# CH1-Isolation.net
KiCad netlist of a schematic drawn in Altium Designer
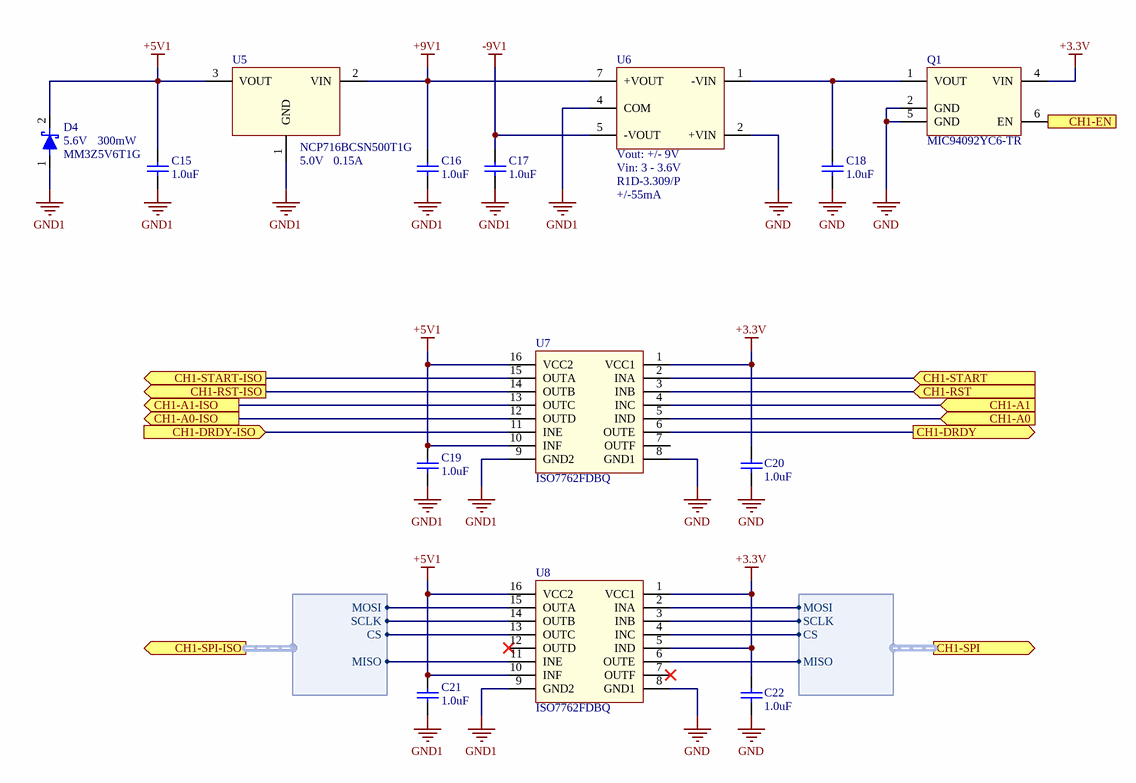
[diagram p0: CH1-Isolation.SchDoc]

(export (version "E")
  (design (tool "Eeschema 10.0.6"))
  (components
    (comp (ref "C15")
      (value "1.0uF")
      (footprint "CAP-0603")
      (description "CAP CER 1uF 25V X7R 0603")
      (fields (field (name "PARTNUMBER") "C0603C105M3RAC7867") (field (name "MANUFACTURER") "Kemet"))
      (libsource (lib "Kemet") (part "C0603C105M3RAC7867"))
    )
    (comp (ref "C16")
      (value "1.0uF")
      (footprint "CAP-0603")
      (description "CAP CER 1uF 25V X7R 0603")
      (fields (field (name "PARTNUMBER") "C0603C105M3RAC7867") (field (name "MANUFACTURER") "Kemet"))
      (libsource (lib "Kemet") (part "C0603C105M3RAC7867"))
    )
    (comp (ref "C17")
      (value "1.0uF")
      (footprint "CAP-0603")
      (description "CAP CER 1uF 25V X7R 0603")
      (fields (field (name "PARTNUMBER") "C0603C105M3RAC7867") (field (name "MANUFACTURER") "Kemet"))
      (libsource (lib "Kemet") (part "C0603C105M3RAC7867"))
    )
    (comp (ref "C18")
      (value "1.0uF")
      (footprint "CAP-0603")
      (description "CAP CER 1uF 25V X7R 0603")
      (fields (field (name "PARTNUMBER") "C0603C105M3RAC7867") (field (name "MANUFACTURER") "Kemet"))
      (libsource (lib "Kemet") (part "C0603C105M3RAC7867"))
    )
    (comp (ref "C19")
      (value "1.0uF")
      (footprint "CAP-0603")
      (description "CAP CER 1uF 25V X7R 0603")
      (fields (field (name "PARTNUMBER") "C0603C105M3RAC7867") (field (name "MANUFACTURER") "Kemet"))
      (libsource (lib "Kemet") (part "C0603C105M3RAC7867"))
    )
    (comp (ref "C20")
      (value "1.0uF")
      (footprint "CAP-0603")
      (description "CAP CER 1uF 25V X7R 0603")
      (fields (field (name "PARTNUMBER") "C0603C105M3RAC7867") (field (name "MANUFACTURER") "Kemet"))
      (libsource (lib "Kemet") (part "C0603C105M3RAC7867"))
    )
    (comp (ref "C21")
      (value "1.0uF")
      (footprint "CAP-0603")
      (description "CAP CER 1uF 25V X7R 0603")
      (fields (field (name "PARTNUMBER") "C0603C105M3RAC7867") (field (name "MANUFACTURER") "Kemet"))
      (libsource (lib "Kemet") (part "C0603C105M3RAC7867"))
    )
    (comp (ref "C22")
      (value "1.0uF")
      (footprint "CAP-0603")
      (description "CAP CER 1uF 25V X7R 0603")
      (fields (field (name "PARTNUMBER") "C0603C105M3RAC7867") (field (name "MANUFACTURER") "Kemet"))
      (libsource (lib "Kemet") (part "C0603C105M3RAC7867"))
    )
    (comp (ref "D4")
      (value "MM3Z5V6T1G")
      (footprint "SOD323 - DIODE UNIDIR")
      (description "Schottky Diode 30V 200mA SOT323")
      (fields
        (field (name "MANUFACTURER") "OnSemiconductor")
        (field (name "POWER") "300mW")
        (field (name "VZ") "5.6V")
        (field (name "PARTNUMBER") "MM3Z5V6T1G")
      )
      (libsource (lib "OnSemiconductors") (part "MM3Z5V6T1G"))
    )
    (comp (ref "Q1")
      (value "MIC94092YC6-TR")
      (footprint "TSSOP6")
      (fields (field (name "MANUFACTURER") "Microchip") (field (name "PARTNUMBER") "MIC94092YC6-TR"))
      (libsource (lib "Microchip") (part "MIC94092YC6-TR"))
    )
    (comp (ref "U5")
      (value "NCP716BCSN500T1G")
      (footprint "SOT23-5")
      (description "IC REG LDO 0.5V 0.15A TSOT23-5")
      (fields
        (field (name "MANUFACTURER") "ON Semiconductor")
        (field (name "PARTNUMBER") "NCP716BCSN500T1G")
        (field (name "VOLTAGE") "5.0V")
        (field (name "CURRENT") "0.15A")
      )
      (libsource (lib "OnSemiconductors") (part "NCP716BCSN500T1G"))
    )
    (comp (ref "U6")
      (value "R1D-3.309/P")
      (footprint "RECOM-R1D")
      (description "DC DC CONVERTER +/-9V 1W")
      (fields
        (field (name "MANUFACTURER") "Recom")
        (field (name "VOUT") "+/- 9V")
        (field (name "VIN") "3 - 3.6V")
        (field (name "PART NUMBER") "R1D-3.309/P")
        (field (name "CURRENT") "+/-55mA")
      )
      (libsource (lib "Recom") (part "R1D-3.309/P"))
    )
    (comp (ref "U7")
      (value "ISO7762FDBQ")
      (footprint "SSOP16")
      (description "Digital Isolator, six-channel, 4/2, 16-SSOP")
      (fields (field (name "MANUFACTURER") "Texas Instruments") (field (name "PARTNUMBER") "ISO7762FDBQ"))
      (libsource (lib "TexasInstruments") (part "ISO7762FDBQ"))
    )
    (comp (ref "U8")
      (value "ISO7762FDBQ")
      (footprint "SSOP16")
      (description "Digital Isolator, six-channel, 4/2, 16-SSOP")
      (fields (field (name "MANUFACTURER") "Texas Instruments") (field (name "PARTNUMBER") "ISO7762FDBQ"))
      (libsource (lib "TexasInstruments") (part "ISO7762FDBQ"))
    )
  )
  (nets
    (net (code "3") (name "+3.3V") (class "Default")
      (node (ref "C20") (pin "2") (pinfunction "2_2") (pintype "passive"))
      (node (ref "C22") (pin "2") (pinfunction "2_2") (pintype "passive"))
      (node (ref "Q1") (pin "4") (pinfunction "VIN_4") (pintype "passive"))
      (node (ref "U7") (pin "1") (pinfunction "VCC1_1") (pintype "passive"))
      (node (ref "U8") (pin "1") (pinfunction "VCC1_1") (pintype "passive"))
      (node (ref "U8") (pin "5") (pinfunction "IND_5") (pintype "passive"))
    )
    (net (code "4") (name "+5V1") (class "Default")
      (node (ref "C15") (pin "2") (pinfunction "2_2") (pintype "passive"))
      (node (ref "C19") (pin "2") (pinfunction "2_2") (pintype "passive"))
      (node (ref "C21") (pin "2") (pinfunction "2_2") (pintype "passive"))
      (node (ref "D4") (pin "2") (pinfunction "K_2") (pintype "passive"))
      (node (ref "U5") (pin "3") (pinfunction "VOUT_3") (pintype "passive"))
      (node (ref "U7") (pin "10") (pinfunction "INF_10") (pintype "passive"))
      (node (ref "U7") (pin "16") (pinfunction "VCC2_16") (pintype "passive"))
      (node (ref "U8") (pin "10") (pinfunction "INF_10") (pintype "passive"))
      (node (ref "U8") (pin "16") (pinfunction "VCC2_16") (pintype "passive"))
    )
    (net (code "5") (name "+9V1") (class "Default")
      (node (ref "C16") (pin "2") (pinfunction "2_2") (pintype "passive"))
      (node (ref "U5") (pin "2") (pinfunction "VIN_2") (pintype "passive"))
      (node (ref "U6") (pin "7") (pinfunction "+VOUT_7") (pintype "passive"))
    )
    (net (code "6") (name "-9V1") (class "Default")
      (node (ref "C17") (pin "2") (pinfunction "2_2") (pintype "passive"))
      (node (ref "U6") (pin "5") (pinfunction "-VOUT_5") (pintype "passive"))
    )
    (net (code "7") (name "/CH1-A0") (class "Default")
      (node (ref "U7") (pin "5") (pinfunction "IND_5") (pintype "passive"))
    )
    (net (code "8") (name "/CH1-A0-ISO") (class "Default")
      (node (ref "U7") (pin "12") (pinfunction "OUTD_12") (pintype "passive"))
    )
    (net (code "9") (name "/CH1-A1") (class "Default")
      (node (ref "U7") (pin "4") (pinfunction "INC_4") (pintype "passive"))
    )
    (net (code "10") (name "/CH1-A1-ISO") (class "Default")
      (node (ref "U7") (pin "13") (pinfunction "OUTC_13") (pintype "passive"))
    )
    (net (code "11") (name "/CH1-DRDY") (class "Default")
      (node (ref "U7") (pin "6") (pinfunction "OUTE_6") (pintype "passive"))
    )
    (net (code "12") (name "/CH1-DRDY-ISO") (class "Default")
      (node (ref "U7") (pin "11") (pinfunction "INE_11") (pintype "passive"))
    )
    (net (code "13") (name "/CH1-EN") (class "Default")
      (node (ref "Q1") (pin "6") (pinfunction "EN_6") (pintype "passive"))
    )
    (net (code "14") (name "/CH1-RST") (class "Default")
      (node (ref "U7") (pin "3") (pinfunction "INB_3") (pintype "passive"))
    )
    (net (code "15") (name "/CH1-RST-ISO") (class "Default")
      (node (ref "U7") (pin "14") (pinfunction "OUTB_14") (pintype "passive"))
    )
    (net (code "16") (name "/CH1-START") (class "Default")
      (node (ref "U7") (pin "2") (pinfunction "INA_2") (pintype "passive"))
    )
    (net (code "17") (name "/CH1-START-ISO") (class "Default")
      (node (ref "U7") (pin "15") (pinfunction "OUTA_15") (pintype "passive"))
    )
    (net (code "20") (name "GND") (class "Default")
      (node (ref "C18") (pin "1") (pinfunction "1_1") (pintype "passive"))
      (node (ref "C20") (pin "1") (pinfunction "1_1") (pintype "passive"))
      (node (ref "C22") (pin "1") (pinfunction "1_1") (pintype "passive"))
      (node (ref "Q1") (pin "2") (pinfunction "GND_2") (pintype "passive"))
      (node (ref "Q1") (pin "5") (pinfunction "GND_5") (pintype "passive"))
      (node (ref "U6") (pin "2") (pinfunction "+VIN_2") (pintype "passive"))
      (node (ref "U7") (pin "8") (pinfunction "GND1_8") (pintype "passive"))
      (node (ref "U8") (pin "8") (pinfunction "GND1_8") (pintype "passive"))
    )
    (net (code "21") (name "GND1") (class "Default")
      (node (ref "C15") (pin "1") (pinfunction "1_1") (pintype "passive"))
      (node (ref "C16") (pin "1") (pinfunction "1_1") (pintype "passive"))
      (node (ref "C17") (pin "1") (pinfunction "1_1") (pintype "passive"))
      (node (ref "C19") (pin "1") (pinfunction "1_1") (pintype "passive"))
      (node (ref "C21") (pin "1") (pinfunction "1_1") (pintype "passive"))
      (node (ref "D4") (pin "1") (pinfunction "A_1") (pintype "passive"))
      (node (ref "U5") (pin "1") (pinfunction "GND_1") (pintype "passive"))
      (node (ref "U6") (pin "4") (pinfunction "COM_4") (pintype "passive"))
      (node (ref "U7") (pin "9") (pinfunction "GND2_9") (pintype "passive"))
      (node (ref "U8") (pin "9") (pinfunction "GND2_9") (pintype "passive"))
    )
    (net (code "22") (name "Net-(Q1-VOUT)") (class "Default")
      (node (ref "C18") (pin "2") (pinfunction "2_2") (pintype "passive"))
      (node (ref "Q1") (pin "1") (pinfunction "VOUT_1") (pintype "passive"))
      (node (ref "U6") (pin "1") (pinfunction "-VIN_1") (pintype "passive"))
    )
    (net (code "23") (name "unconnected-(U7-OUTF-Pad7)") (class "Default")
      (node (ref "U7") (pin "7") (pinfunction "OUTF_7") (pintype "passive"))
    )
    (net (code "24") (name "unconnected-(U8-INA-Pad2)") (class "Default")
      (node (ref "U8") (pin "2") (pinfunction "INA_2") (pintype "passive"))
    )
    (net (code "25") (name "unconnected-(U8-INB-Pad3)") (class "Default")
      (node (ref "U8") (pin "3") (pinfunction "INB_3") (pintype "passive"))
    )
    (net (code "26") (name "unconnected-(U8-INC-Pad4)") (class "Default")
      (node (ref "U8") (pin "4") (pinfunction "INC_4") (pintype "passive"))
    )
    (net (code "27") (name "unconnected-(U8-INE-Pad11)") (class "Default")
      (node (ref "U8") (pin "11") (pinfunction "INE_11") (pintype "passive"))
    )
    (net (code "28") (name "unconnected-(U8-OUTA-Pad15)") (class "Default")
      (node (ref "U8") (pin "15") (pinfunction "OUTA_15") (pintype "passive"))
    )
    (net (code "29") (name "unconnected-(U8-OUTB-Pad14)") (class "Default")
      (node (ref "U8") (pin "14") (pinfunction "OUTB_14") (pintype "passive"))
    )
    (net (code "30") (name "unconnected-(U8-OUTC-Pad13)") (class "Default")
      (node (ref "U8") (pin "13") (pinfunction "OUTC_13") (pintype "passive"))
    )
    (net (code "31") (name "unconnected-(U8-OUTD-Pad12)") (class "Default")
      (node (ref "U8") (pin "12") (pinfunction "OUTD_12") (pintype "passive+no_connect"))
    )
    (net (code "32") (name "unconnected-(U8-OUTE-Pad6)") (class "Default")
      (node (ref "U8") (pin "6") (pinfunction "OUTE_6") (pintype "passive"))
    )
    (net (code "33") (name "unconnected-(U8-OUTF-Pad7)") (class "Default")
      (node (ref "U8") (pin "7") (pinfunction "OUTF_7") (pintype "passive+no_connect"))
    )
  )
)
